# Spectra6PCB_71.net
KiCad netlist of a schematic drawn in EAGLE
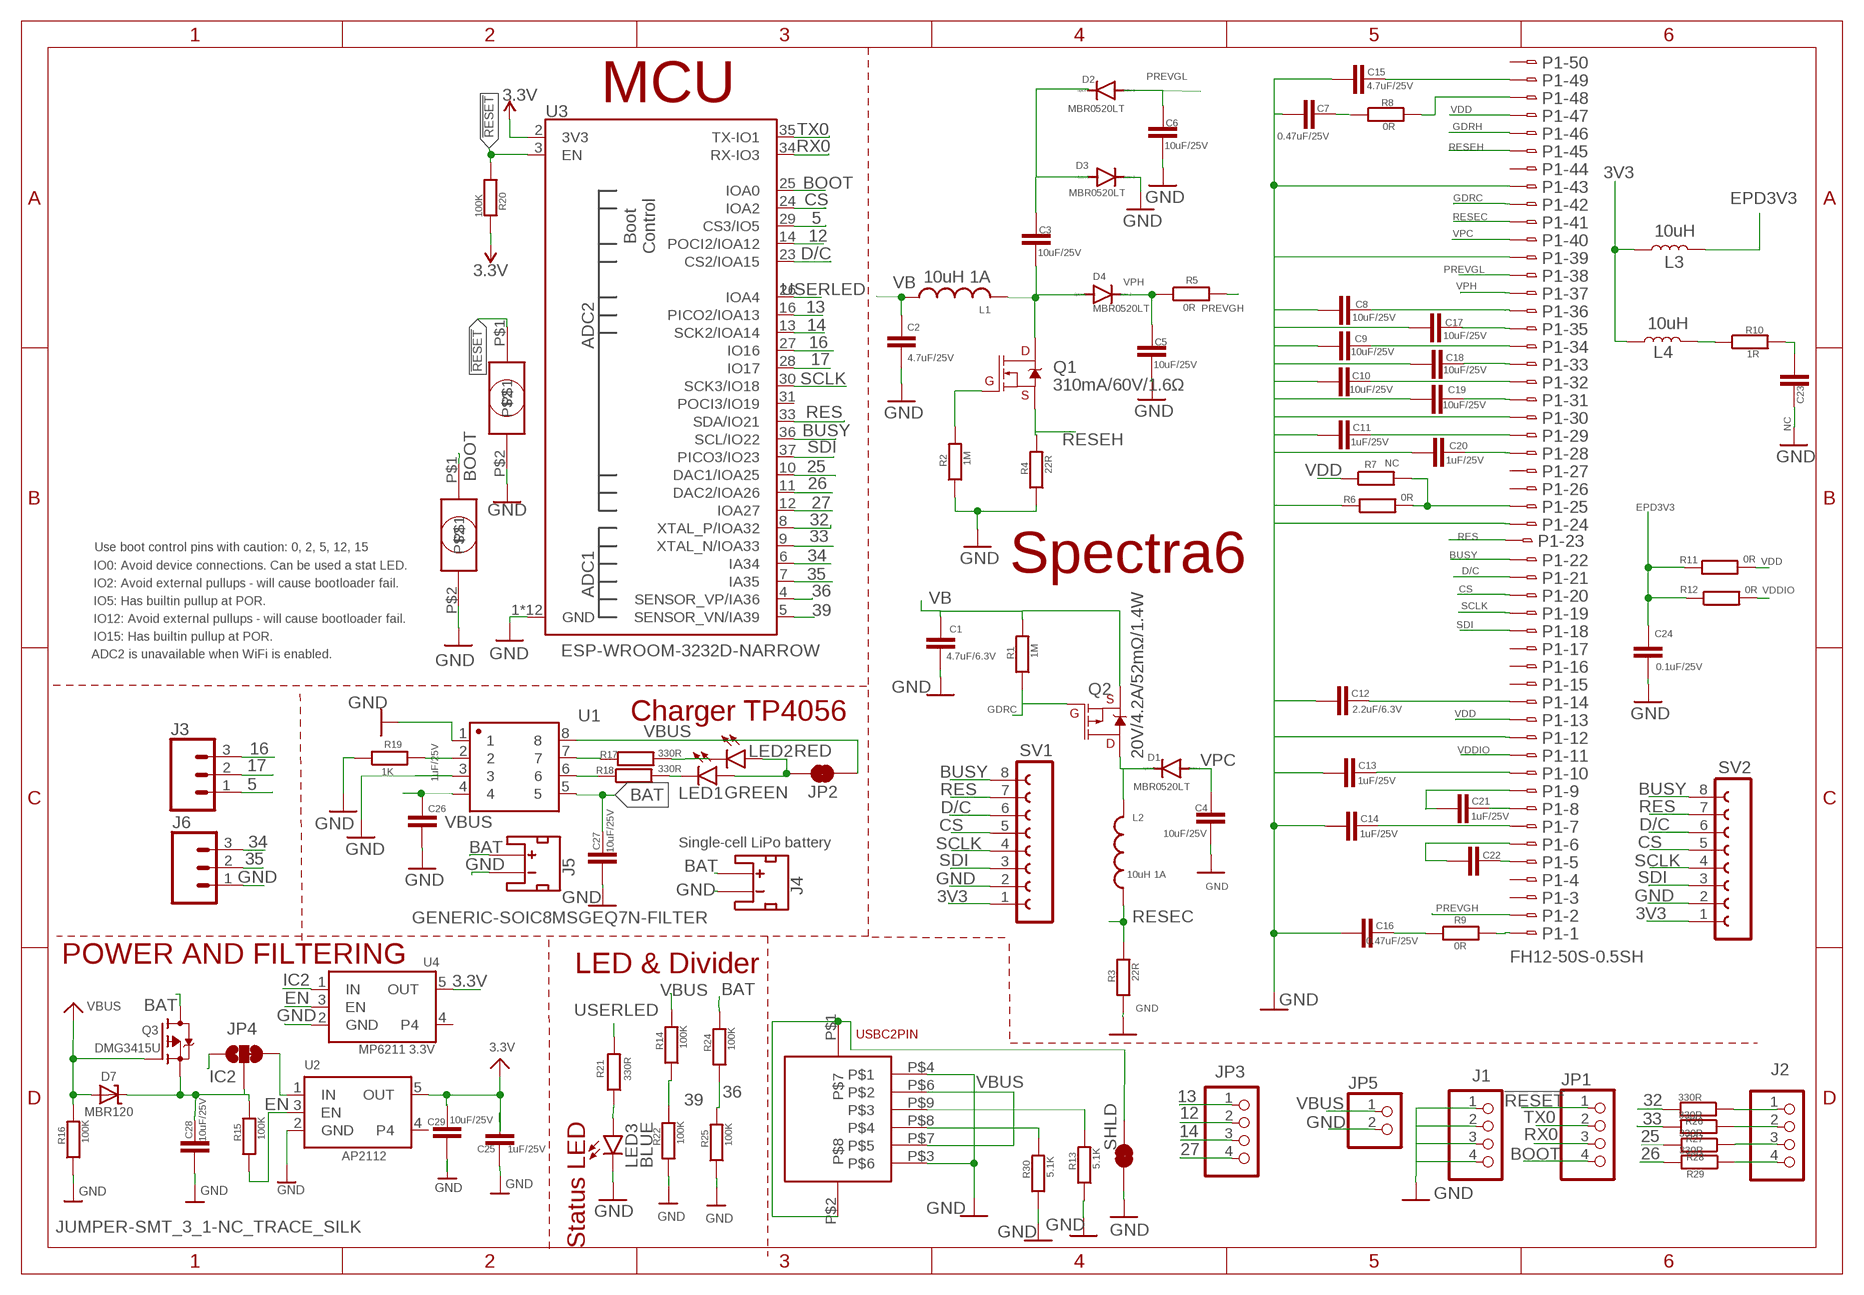
[diagram p0: schematic, sheet 1]

(export (version "E")
  (design (tool "Eeschema 10.0.6"))
  (components
    (comp (ref "C1")
      (value "4.7uF/6.3V")
      (footprint "eagle-import:C0805")
      (libsource (lib "eagle-import") (part "C-EUC0805"))
    )
    (comp (ref "C2")
      (value "4.7uF/25V")
      (footprint "eagle-import:C0805")
      (libsource (lib "eagle-import") (part "C-EUC0805"))
    )
    (comp (ref "C3")
      (value "10uF/25V")
      (footprint "eagle-import:C0805")
      (libsource (lib "eagle-import") (part "C-EUC0805"))
    )
    (comp (ref "C4")
      (value "10uF/25V")
      (footprint "eagle-import:C0805")
      (libsource (lib "eagle-import") (part "C-EUC0805"))
    )
    (comp (ref "C5")
      (value "10uF/25V")
      (footprint "eagle-import:C0805")
      (libsource (lib "eagle-import") (part "C-EUC0805"))
    )
    (comp (ref "C6")
      (value "10uF/25V")
      (footprint "eagle-import:C0805")
      (libsource (lib "eagle-import") (part "C-EUC0805"))
    )
    (comp (ref "C7")
      (value "0.47uF/25V")
      (footprint "eagle-import:C0805")
      (libsource (lib "eagle-import") (part "C-EUC0805"))
    )
    (comp (ref "C8")
      (value "10uF/25V")
      (footprint "eagle-import:C0805")
      (libsource (lib "eagle-import") (part "C-EUC0805"))
    )
    (comp (ref "C9")
      (value "10uF/25V")
      (footprint "eagle-import:C0805")
      (libsource (lib "eagle-import") (part "C-EUC0805"))
    )
    (comp (ref "C10")
      (value "10uF/25V")
      (footprint "eagle-import:C0805")
      (libsource (lib "eagle-import") (part "C-EUC0805"))
    )
    (comp (ref "C11")
      (value "1uF/25V")
      (footprint "eagle-import:C0805")
      (libsource (lib "eagle-import") (part "C-EUC0805"))
    )
    (comp (ref "C12")
      (value "2.2uF/6.3V")
      (footprint "eagle-import:C0805")
      (libsource (lib "eagle-import") (part "C-EUC0805"))
    )
    (comp (ref "C13")
      (value "1uF/25V")
      (footprint "eagle-import:C0805")
      (libsource (lib "eagle-import") (part "C-EUC0805"))
    )
    (comp (ref "C14")
      (value "1uF/25V")
      (footprint "eagle-import:C0805")
      (libsource (lib "eagle-import") (part "C-EUC0805"))
    )
    (comp (ref "C15")
      (value "4.7uF/25V")
      (footprint "eagle-import:C0805")
      (libsource (lib "eagle-import") (part "C-EUC0805"))
    )
    (comp (ref "C16")
      (value "0.47uF/25V")
      (footprint "eagle-import:C0805")
      (libsource (lib "eagle-import") (part "C-EUC0805"))
    )
    (comp (ref "C17")
      (value "10uF/25V")
      (footprint "eagle-import:C0805")
      (libsource (lib "eagle-import") (part "C-EUC0805"))
    )
    (comp (ref "C18")
      (value "10uF/25V")
      (footprint "eagle-import:C0805")
      (libsource (lib "eagle-import") (part "C-EUC0805"))
    )
    (comp (ref "C19")
      (value "10uF/25V")
      (footprint "eagle-import:C0805")
      (libsource (lib "eagle-import") (part "C-EUC0805"))
    )
    (comp (ref "C20")
      (value "1uF/25V")
      (footprint "eagle-import:C0805")
      (libsource (lib "eagle-import") (part "C-EUC0805"))
    )
    (comp (ref "C21")
      (value "1uF/25V")
      (footprint "eagle-import:C0805")
      (libsource (lib "eagle-import") (part "C-EUC0805"))
    )
    (comp (ref "C22")
      (value "1uF/25V")
      (footprint "eagle-import:C0805")
      (libsource (lib "eagle-import") (part "C-EUC0805"))
    )
    (comp (ref "C23")
      (value "NC")
      (footprint "eagle-import:C0805")
      (libsource (lib "eagle-import") (part "C-EUC0805"))
    )
    (comp (ref "C24")
      (value "0.1uF/25V")
      (footprint "eagle-import:C0805")
      (libsource (lib "eagle-import") (part "C-EUC0805"))
    )
    (comp (ref "C25")
      (value "1uF/25V")
      (footprint "eagle-import:C0805")
      (libsource (lib "eagle-import") (part "C-EUC0805"))
    )
    (comp (ref "C26")
      (value "1uF/25V")
      (footprint "eagle-import:C0805")
      (libsource (lib "eagle-import") (part "C-EUC0805"))
    )
    (comp (ref "C27")
      (value "10uF/25V")
      (footprint "eagle-import:C0805")
      (libsource (lib "eagle-import") (part "C-EUC0805"))
    )
    (comp (ref "C28")
      (value "10uF/25V")
      (footprint "eagle-import:C0805")
      (libsource (lib "eagle-import") (part "C-EUC0805"))
    )
    (comp (ref "C29")
      (value "10uF/25V")
      (footprint "eagle-import:C0805")
      (libsource (lib "eagle-import") (part "C-EUC0805"))
    )
    (comp (ref "D1")
      (value "MBR0520LT")
      (footprint "eagle-import:SOD123")
      (libsource (lib "eagle-import") (part "MBR0520LT"))
    )
    (comp (ref "D2")
      (value "MBR0520LT")
      (footprint "eagle-import:SOD123")
      (libsource (lib "eagle-import") (part "MBR0520LT"))
    )
    (comp (ref "D3")
      (value "MBR0520LT")
      (footprint "eagle-import:SOD123")
      (libsource (lib "eagle-import") (part "MBR0520LT"))
    )
    (comp (ref "D4")
      (value "MBR0520LT")
      (footprint "eagle-import:SOD123")
      (libsource (lib "eagle-import") (part "MBR0520LT"))
    )
    (comp (ref "D7")
      (value "MBR120")
      (footprint "eagle-import:SOD-123")
      (libsource (lib "eagle-import") (part "DIODE-SCHOTTKYSOD-123"))
    )
    (comp (ref "J1")
      (value "PINHD-1X4")
      (footprint "eagle-import:1X04")
      (libsource (lib "eagle-import") (part "PINHD-1X4"))
    )
    (comp (ref "J2")
      (value "PINHD-1X4")
      (footprint "eagle-import:1X04")
      (libsource (lib "eagle-import") (part "PINHD-1X4"))
    )
    (comp (ref "J3")
      (value "CONN_03PAD")
      (footprint "eagle-import:1X03_SOLDER_PADS")
      (libsource (lib "eagle-import") (part "CONN_03PAD"))
    )
    (comp (ref "J4")
      (value "JST_2MM_MALE")
      (footprint "eagle-import:JST-2-SMD")
      (libsource (lib "eagle-import") (part "JST_2MM_MALE"))
    )
    (comp (ref "J5")
      (value "NC")
      (footprint "eagle-import:JST-2-SMD")
      (libsource (lib "eagle-import") (part "JST_2MM_MALE"))
    )
    (comp (ref "J6")
      (value "CONN_03PAD")
      (footprint "eagle-import:1X03_SOLDER_PADS")
      (libsource (lib "eagle-import") (part "CONN_03PAD"))
    )
    (comp (ref "JP1")
      (value "PINHD-1X4")
      (footprint "eagle-import:1X04")
      (libsource (lib "eagle-import") (part "PINHD-1X4"))
    )
    (comp (ref "JP2")
      (value "JUMPER-SMT_2_NC_TRACE_SILK")
      (footprint "eagle-import:SMT-JUMPER_2_NC_TRACE_SILK")
      (libsource (lib "eagle-import") (part "JUMPER-SMT_2_NC_TRACE_SILK"))
    )
    (comp (ref "JP3")
      (value "PINHD-1X4")
      (footprint "eagle-import:1X04")
      (libsource (lib "eagle-import") (part "PINHD-1X4"))
    )
    (comp (ref "JP4")
      (value "JUMPER-SMT_3_1-NC_TRACE_SILK")
      (footprint "eagle-import:SMT-JUMPER_3_1-NC_TRACE_SILK")
      (libsource (lib "eagle-import") (part "JUMPER-SMT_3_1-NC_TRACE_SILK"))
    )
    (comp (ref "JP5")
      (value "PINHD-1X2")
      (footprint "eagle-import:1X02")
      (libsource (lib "eagle-import") (part "PINHD-1X2"))
    )
    (comp (ref "L1")
      (value "10uH 1A")
      (footprint "eagle-import:L4035M")
      (libsource (lib "eagle-import") (part "L-USL4035M"))
    )
    (comp (ref "L2")
      (value "10uH 1A")
      (footprint "eagle-import:L4035M")
      (libsource (lib "eagle-import") (part "L-USL4035M"))
    )
    (comp (ref "L3")
      (value "10uH")
      (footprint "eagle-import:0805")
      (libsource (lib "eagle-import") (part "INDUCTOR-0805-3.3UH"))
    )
    (comp (ref "L4")
      (value "10uH")
      (footprint "eagle-import:0805")
      (libsource (lib "eagle-import") (part "INDUCTOR-0805-3.3UH"))
    )
    (comp (ref "LED1")
      (value "GREEN")
      (footprint "eagle-import:SML0805")
      (libsource (lib "eagle-import") (part "LEDSML0805"))
    )
    (comp (ref "LED2")
      (value "RED")
      (footprint "eagle-import:SML0805")
      (libsource (lib "eagle-import") (part "LEDSML0805"))
    )
    (comp (ref "LED3")
      (value "BLUE")
      (footprint "eagle-import:SML0805")
      (libsource (lib "eagle-import") (part "LEDSML0805"))
    )
    (comp (ref "P1")
      (value "FH12-50S-0.5SH")
      (footprint "eagle-import:FH12-50S-0.5SH")
      (fields (field (name "MPN") "FH12-50S-0.5SH(55)"))
      (libsource (lib "eagle-import") (part "FH12-50S-0.5SH"))
    )
    (comp (ref "Q1")
      (value "310mA/60V/1.6Ω")
      (footprint "eagle-import:SOT323")
      (libsource (lib "eagle-import") (part "MOSFET-NCH-2N7002PW"))
    )
    (comp (ref "Q2")
      (value "20V/4.2A/52mΩ/1.4W")
      (footprint "eagle-import:SOT23-3")
      (libsource (lib "eagle-import") (part "MOSFET_PCH-DMG2305UX-7"))
    )
    (comp (ref "Q3")
      (value "DMG3415U")
      (footprint "eagle-import:SOT23-R")
      (libsource (lib "eagle-import") (part "MOSFET-P"))
    )
    (comp (ref "R1")
      (value "1M")
      (footprint "eagle-import:M0805")
      (libsource (lib "eagle-import") (part "R-EU_M0805"))
    )
    (comp (ref "R2")
      (value "1M")
      (footprint "eagle-import:M0805")
      (libsource (lib "eagle-import") (part "R-EU_M0805"))
    )
    (comp (ref "R3")
      (value "22R")
      (footprint "eagle-import:M0805")
      (libsource (lib "eagle-import") (part "R-EU_M0805"))
    )
    (comp (ref "R4")
      (value "22R")
      (footprint "eagle-import:M0805")
      (libsource (lib "eagle-import") (part "R-EU_M0805"))
    )
    (comp (ref "R5")
      (value "0R")
      (footprint "eagle-import:M0805")
      (libsource (lib "eagle-import") (part "R-EU_M0805"))
    )
    (comp (ref "R6")
      (value "0R")
      (footprint "eagle-import:M0805")
      (libsource (lib "eagle-import") (part "R-EU_M0805"))
    )
    (comp (ref "R7")
      (value "NC")
      (footprint "eagle-import:M0805")
      (libsource (lib "eagle-import") (part "R-EU_M0805"))
    )
    (comp (ref "R8")
      (value "0R")
      (footprint "eagle-import:M0805")
      (libsource (lib "eagle-import") (part "R-EU_M0805"))
    )
    (comp (ref "R9")
      (value "0R")
      (footprint "eagle-import:M0805")
      (libsource (lib "eagle-import") (part "R-EU_M0805"))
    )
    (comp (ref "R10")
      (value "1R")
      (footprint "eagle-import:M0805")
      (libsource (lib "eagle-import") (part "R-EU_M0805"))
    )
    (comp (ref "R11")
      (value "0R")
      (footprint "eagle-import:M0805")
      (libsource (lib "eagle-import") (part "R-EU_M0805"))
    )
    (comp (ref "R12")
      (value "0R")
      (footprint "eagle-import:M0805")
      (libsource (lib "eagle-import") (part "R-EU_M0805"))
    )
    (comp (ref "R13")
      (value "5.1K")
      (footprint "eagle-import:M0805")
      (libsource (lib "eagle-import") (part "R-EU_M0805"))
    )
    (comp (ref "R14")
      (value "100K")
      (footprint "eagle-import:M0805")
      (libsource (lib "eagle-import") (part "R-EU_M0805"))
    )
    (comp (ref "R15")
      (value "100K")
      (footprint "eagle-import:M0805")
      (libsource (lib "eagle-import") (part "R-EU_M0805"))
    )
    (comp (ref "R16")
      (value "100K")
      (footprint "eagle-import:M0805")
      (libsource (lib "eagle-import") (part "R-EU_M0805"))
    )
    (comp (ref "R17")
      (value "330R")
      (footprint "eagle-import:M0805")
      (libsource (lib "eagle-import") (part "R-EU_M0805"))
    )
    (comp (ref "R18")
      (value "330R")
      (footprint "eagle-import:M0805")
      (libsource (lib "eagle-import") (part "R-EU_M0805"))
    )
    (comp (ref "R19")
      (value "1K")
      (footprint "eagle-import:M0805")
      (libsource (lib "eagle-import") (part "R-EU_M0805"))
    )
    (comp (ref "R20")
      (value "100K")
      (footprint "eagle-import:M0805")
      (libsource (lib "eagle-import") (part "R-EU_M0805"))
    )
    (comp (ref "R21")
      (value "330R")
      (footprint "eagle-import:M0805")
      (libsource (lib "eagle-import") (part "R-EU_M0805"))
    )
    (comp (ref "R22")
      (value "100K")
      (footprint "eagle-import:M0805")
      (libsource (lib "eagle-import") (part "R-EU_M0805"))
    )
    (comp (ref "R24")
      (value "100K")
      (footprint "eagle-import:M0805")
      (libsource (lib "eagle-import") (part "R-EU_M0805"))
    )
    (comp (ref "R25")
      (value "100K")
      (footprint "eagle-import:M0805")
      (libsource (lib "eagle-import") (part "R-EU_M0805"))
    )
    (comp (ref "R26")
      (value "330R")
      (footprint "eagle-import:M0805")
      (libsource (lib "eagle-import") (part "R-EU_M0805"))
    )
    (comp (ref "R27")
      (value "330R")
      (footprint "eagle-import:M0805")
      (libsource (lib "eagle-import") (part "R-EU_M0805"))
    )
    (comp (ref "R28")
      (value "330R")
      (footprint "eagle-import:M0805")
      (libsource (lib "eagle-import") (part "R-EU_M0805"))
    )
    (comp (ref "R29")
      (value "330R")
      (footprint "eagle-import:M0805")
      (libsource (lib "eagle-import") (part "R-EU_M0805"))
    )
    (comp (ref "R30")
      (value "5.1K")
      (footprint "eagle-import:M0805")
      (libsource (lib "eagle-import") (part "R-EU_M0805"))
    )
    (comp (ref "S3")
      (value "TACTILE")
      (footprint "eagle-import:TACTILE")
      (libsource (lib "eagle-import") (part "TACTILE"))
    )
    (comp (ref "S4")
      (value "TACTILE")
      (footprint "eagle-import:TACTILE")
      (libsource (lib "eagle-import") (part "TACTILE"))
    )
    (comp (ref "SHLD")
      (value "SHLD")
      (footprint "eagle-import:SMT-JUMPER_2_NC_TRACE_NO-SILK")
      (libsource (lib "eagle-import") (part "JUMPER-SMT_2_NC_TRACE_NO-SILK"))
    )
    (comp (ref "SV1")
      (value "FE08-1")
      (footprint "eagle-import:FE08")
      (libsource (lib "eagle-import") (part "FE08-1"))
    )
    (comp (ref "SV2")
      (value "FE08-1")
      (footprint "eagle-import:FE08")
      (libsource (lib "eagle-import") (part "FE08-1"))
    )
    (comp (ref "U$4")
      (value "USBC6PIN")
      (footprint "eagle-import:USBC6PIN")
      (libsource (lib "eagle-import") (part "USBC6PIN"))
    )
    (comp (ref "U1")
      (value "GENERIC-SOIC8MSGEQ7N-FILTER")
      (footprint "eagle-import:SO08")
      (libsource (lib "eagle-import") (part "GENERIC-SOIC8MSGEQ7N-FILTER"))
    )
    (comp (ref "U2")
      (value "AP2112")
      (footprint "eagle-import:SOT23-5")
      (libsource (lib "eagle-import") (part "VREG_SOT23-5"))
    )
    (comp (ref "U3")
      (value "ESP-WROOM-3232D-NARROW")
      (footprint "eagle-import:ESP-WROOM-32D-NARROW")
      (libsource (lib "eagle-import") (part "ESP-WROOM-3232D-NARROW"))
    )
    (comp (ref "U4")
      (value "MP6211 3.3V")
      (footprint "eagle-import:SOT23-5")
      (libsource (lib "eagle-import") (part "VREG_SOT23-5"))
    )
  )
  (nets
    (net (code "1") (name "/3V3") (class "Default")
      (node (ref "L3") (pin "1") (pinfunction "1_1") (pintype "passive"))
      (node (ref "L4") (pin "1") (pinfunction "1_1") (pintype "passive"))
      (node (ref "SV1") (pin "1") (pinfunction "1_1") (pintype "passive"))
      (node (ref "SV2") (pin "1") (pinfunction "1_1") (pintype "passive"))
    )
    (net (code "2") (name "/5") (class "Default")
      (node (ref "J3") (pin "1") (pinfunction "1_1") (pintype "passive"))
      (node (ref "U3") (pin "29") (pinfunction "CS3/IO5_29") (pintype "bidirectional"))
    )
    (net (code "3") (name "/12") (class "Default")
      (node (ref "JP3") (pin "2") (pinfunction "2_2") (pintype "passive"))
      (node (ref "U3") (pin "14") (pinfunction "POCI2/IOA12_14") (pintype "bidirectional"))
    )
    (net (code "4") (name "/13") (class "Default")
      (node (ref "JP3") (pin "1") (pinfunction "1_1") (pintype "passive"))
      (node (ref "U3") (pin "16") (pinfunction "PICO2/IOA13_16") (pintype "bidirectional"))
    )
    (net (code "5") (name "/14") (class "Default")
      (node (ref "JP3") (pin "3") (pinfunction "3_3") (pintype "passive"))
      (node (ref "U3") (pin "13") (pinfunction "SCK2/IOA14_13") (pintype "bidirectional"))
    )
    (net (code "6") (name "/16") (class "Default")
      (node (ref "J3") (pin "3") (pinfunction "3_3") (pintype "passive"))
      (node (ref "U3") (pin "27") (pinfunction "IO16_27") (pintype "bidirectional"))
    )
    (net (code "7") (name "/17") (class "Default")
      (node (ref "J3") (pin "2") (pinfunction "2_2") (pintype "passive"))
      (node (ref "U3") (pin "28") (pinfunction "IO17_28") (pintype "bidirectional"))
    )
    (net (code "8") (name "/25") (class "Default")
      (node (ref "R28") (pin "2") (pinfunction "2_2") (pintype "passive"))
      (node (ref "U3") (pin "10") (pinfunction "DAC1/IOA25_10") (pintype "bidirectional"))
    )
    (net (code "9") (name "/26") (class "Default")
      (node (ref "R29") (pin "2") (pinfunction "2_2") (pintype "passive"))
      (node (ref "U3") (pin "11") (pinfunction "DAC2/IOA26_11") (pintype "bidirectional"))
    )
    (net (code "10") (name "/27") (class "Default")
      (node (ref "JP3") (pin "4") (pinfunction "4_4") (pintype "passive"))
      (node (ref "U3") (pin "12") (pinfunction "IOA27_12") (pintype "bidirectional"))
    )
    (net (code "11") (name "/32") (class "Default")
      (node (ref "R26") (pin "2") (pinfunction "2_2") (pintype "passive"))
      (node (ref "U3") (pin "8") (pinfunction "XTAL_P/IOA32_8") (pintype "bidirectional"))
    )
    (net (code "12") (name "/33") (class "Default")
      (node (ref "R27") (pin "2") (pinfunction "2_2") (pintype "passive"))
      (node (ref "U3") (pin "9") (pinfunction "XTAL_N/IOA33_9") (pintype "bidirectional"))
    )
    (net (code "13") (name "/34") (class "Default")
      (node (ref "J6") (pin "3") (pinfunction "3_3") (pintype "passive"))
      (node (ref "U3") (pin "6") (pinfunction "IA34_6") (pintype "bidirectional"))
    )
    (net (code "14") (name "/35") (class "Default")
      (node (ref "J6") (pin "2") (pinfunction "2_2") (pintype "passive"))
      (node (ref "U3") (pin "7") (pinfunction "IA35_7") (pintype "bidirectional"))
    )
    (net (code "15") (name "/36") (class "Default")
      (node (ref "R24") (pin "1") (pinfunction "1_1") (pintype "passive"))
      (node (ref "R25") (pin "2") (pinfunction "2_2") (pintype "passive"))
      (node (ref "U3") (pin "4") (pinfunction "SENSOR_VP/IA36_4") (pintype "bidirectional"))
    )
    (net (code "16") (name "/39") (class "Default")
      (node (ref "R14") (pin "1") (pinfunction "1_1") (pintype "passive"))
      (node (ref "R22") (pin "2") (pinfunction "2_2") (pintype "passive"))
      (node (ref "U3") (pin "5") (pinfunction "SENSOR_VN/IA39_5") (pintype "bidirectional"))
    )
    (net (code "17") (name "/BOOT") (class "Default")
      (node (ref "JP1") (pin "4") (pinfunction "4_4") (pintype "passive"))
      (node (ref "S3") (pin "P$1") (pinfunction "P$1_P$1") (pintype "bidirectional"))
      (node (ref "U3") (pin "25") (pinfunction "IOA0_25") (pintype "bidirectional"))
    )
    (net (code "18") (name "/BUSY") (class "Default")
      (node (ref "P1") (pin "22") (pinfunction "1_22") (pintype "passive"))
      (node (ref "SV1") (pin "8") (pinfunction "8_8") (pintype "passive"))
      (node (ref "SV2") (pin "8") (pinfunction "8_8") (pintype "passive"))
      (node (ref "U3") (pin "36") (pinfunction "SCL/IO22_36") (pintype "bidirectional"))
    )
    (net (code "19") (name "/CS") (class "Default")
      (node (ref "P1") (pin "20") (pinfunction "1_20") (pintype "passive"))
      (node (ref "SV1") (pin "5") (pinfunction "5_5") (pintype "passive"))
      (node (ref "SV2") (pin "5") (pinfunction "5_5") (pintype "passive"))
      (node (ref "U3") (pin "24") (pinfunction "IOA2_24") (pintype "bidirectional"))
    )
    (net (code "20") (name "/D{slash}C") (class "Default")
      (node (ref "P1") (pin "21") (pinfunction "1_21") (pintype "passive"))
      (node (ref "SV1") (pin "6") (pinfunction "6_6") (pintype "passive"))
      (node (ref "SV2") (pin "6") (pinfunction "6_6") (pintype "passive"))
      (node (ref "U3") (pin "23") (pinfunction "CS2/IOA15_23") (pintype "bidirectional"))
    )
    (net (code "21") (name "/EN") (class "Default")
      (node (ref "R15") (pin "1") (pinfunction "1_1") (pintype "passive"))
      (node (ref "U2") (pin "3") (pinfunction "EN_3") (pintype "input"))
      (node (ref "U4") (pin "3") (pinfunction "EN_3") (pintype "input"))
    )
    (net (code "22") (name "/EPD3V3") (class "Default")
      (node (ref "C24") (pin "2") (pinfunction "2_2") (pintype "passive"))
      (node (ref "L3") (pin "2") (pinfunction "2_2") (pintype "passive"))
      (node (ref "R11") (pin "1") (pinfunction "1_1") (pintype "passive"))
      (node (ref "R12") (pin "1") (pinfunction "1_1") (pintype "passive"))
    )
    (net (code "23") (name "/GDRC") (class "Default")
      (node (ref "P1") (pin "42") (pinfunction "1_42") (pintype "passive"))
      (node (ref "Q2") (pin "1") (pinfunction "G_1") (pintype "bidirectional"))
      (node (ref "R1") (pin "1") (pinfunction "1_1") (pintype "passive"))
    )
    (net (code "24") (name "/GDRH") (class "Default")
      (node (ref "P1") (pin "46") (pinfunction "1_46") (pintype "passive"))
      (node (ref "Q1") (pin "1") (pinfunction "G_1") (pintype "bidirectional"))
      (node (ref "R2") (pin "2") (pinfunction "2_2") (pintype "passive"))
    )
    (net (code "25") (name "/IC2") (class "Default")
      (node (ref "JP4") (pin "1") (pinfunction "1_1") (pintype "passive"))
      (node (ref "U4") (pin "1") (pinfunction "IN_1") (pintype "power_in"))
    )
    (net (code "26") (name "/PREVGH") (class "Default")
      (node (ref "P1") (pin "2") (pinfunction "1_2") (pintype "passive"))
      (node (ref "R5") (pin "2") (pinfunction "2_2") (pintype "passive"))
    )
    (net (code "27") (name "/PREVGL") (class "Default")
      (node (ref "C6") (pin "1") (pinfunction "1_1") (pintype "passive"))
      (node (ref "D2") (pin "A") (pinfunction "A_A") (pintype "passive"))
      (node (ref "P1") (pin "38") (pinfunction "1_38") (pintype "passive"))
    )
    (net (code "28") (name "/RES") (class "Default")
      (node (ref "P1") (pin "23") (pinfunction "1_23") (pintype "passive"))
      (node (ref "SV1") (pin "7") (pinfunction "7_7") (pintype "passive"))
      (node (ref "SV2") (pin "7") (pinfunction "7_7") (pintype "passive"))
      (node (ref "U3") (pin "33") (pinfunction "SDA/IO21_33") (pintype "bidirectional"))
    )
    (net (code "29") (name "/RESEC") (class "Default")
      (node (ref "L2") (pin "1") (pinfunction "1_1") (pintype "passive"))
      (node (ref "P1") (pin "41") (pinfunction "1_41") (pintype "passive"))
      (node (ref "R3") (pin "2") (pinfunction "2_2") (pintype "passive"))
    )
    (net (code "30") (name "/RESEH") (class "Default")
      (node (ref "P1") (pin "45") (pinfunction "1_45") (pintype "passive"))
      (node (ref "Q1") (pin "2") (pinfunction "S_2") (pintype "bidirectional"))
      (node (ref "R4") (pin "2") (pinfunction "2_2") (pintype "passive"))
    )
    (net (code "31") (name "/RX0") (class "Default")
      (node (ref "JP1") (pin "3") (pinfunction "3_3") (pintype "passive"))
      (node (ref "U3") (pin "34") (pinfunction "RX-IO3_34") (pintype "bidirectional"))
    )
    (net (code "32") (name "/SCLK") (class "Default")
      (node (ref "P1") (pin "19") (pinfunction "1_19") (pintype "passive"))
      (node (ref "SV1") (pin "4") (pinfunction "4_4") (pintype "passive"))
      (node (ref "SV2") (pin "4") (pinfunction "4_4") (pintype "passive"))
      (node (ref "U3") (pin "30") (pinfunction "SCK3/IO18_30") (pintype "bidirectional"))
    )
    (net (code "33") (name "/SDI") (class "Default")
      (node (ref "P1") (pin "18") (pinfunction "1_18") (pintype "passive"))
      (node (ref "SV1") (pin "3") (pinfunction "3_3") (pintype "passive"))
      (node (ref "SV2") (pin "3") (pinfunction "3_3") (pintype "passive"))
      (node (ref "U3") (pin "37") (pinfunction "PICO3/IO23_37") (pintype "bidirectional"))
    )
    (net (code "34") (name "/TX0") (class "Default")
      (node (ref "JP1") (pin "2") (pinfunction "2_2") (pintype "passive"))
      (node (ref "U3") (pin "35") (pinfunction "TX-IO1_35") (pintype "bidirectional"))
    )
    (net (code "35") (name "/USERLED") (class "Default")
      (node (ref "R21") (pin "2") (pinfunction "2_2") (pintype "passive"))
      (node (ref "U3") (pin "26") (pinfunction "IOA4_26") (pintype "bidirectional"))
    )
    (net (code "36") (name "/VB") (class "Default")
      (node (ref "C2") (pin "2") (pinfunction "2_2") (pintype "passive"))
      (node (ref "L1") (pin "1") (pinfunction "1_1") (pintype "passive"))
    )
    (net (code "37") (name "/VDD") (class "Default")
      (node (ref "P1") (pin "13") (pinfunction "1_13") (pintype "passive"))
      (node (ref "P1") (pin "47") (pinfunction "1_47") (pintype "passive"))
      (node (ref "R11") (pin "2") (pinfunction "2_2") (pintype "passive"))
      (node (ref "R7") (pin "1") (pinfunction "1_1") (pintype "passive"))
    )
    (net (code "38") (name "/VDDIO") (class "Default")
      (node (ref "P1") (pin "11") (pinfunction "1_11") (pintype "passive"))
      (node (ref "R12") (pin "2") (pinfunction "2_2") (pintype "passive"))
    )
    (net (code "39") (name "/VPC") (class "Default")
      (node (ref "C4") (pin "2") (pinfunction "2_2") (pintype "passive"))
      (node (ref "D1") (pin "A") (pinfunction "A_A") (pintype "passive"))
      (node (ref "P1") (pin "40") (pinfunction "1_40") (pintype "passive"))
    )
    (net (code "40") (name "/VPH") (class "Default")
      (node (ref "C5") (pin "1") (pinfunction "1_1") (pintype "passive"))
      (node (ref "D4") (pin "C") (pinfunction "C_C") (pintype "passive"))
      (node (ref "P1") (pin "37") (pinfunction "1_37") (pintype "passive"))
      (node (ref "R5") (pin "1") (pinfunction "1_1") (pintype "passive"))
    )
    (net (code "41") (name "/~{RESET}") (class "Default")
      (node (ref "JP1") (pin "1") (pinfunction "1_1") (pintype "passive"))
      (node (ref "R20") (pin "1") (pinfunction "1_1") (pintype "passive"))
      (node (ref "S4") (pin "P$1") (pinfunction "P$1_P$1") (pintype "bidirectional"))
      (node (ref "U3") (pin "3") (pinfunction "EN_3") (pintype "bidirectional"))
    )
    (net (code "42") (name "3.3V") (class "Default")
      (node (ref "C25") (pin "2") (pinfunction "2_2") (pintype "passive"))
      (node (ref "C29") (pin "2") (pinfunction "2_2") (pintype "passive"))
      (node (ref "R20") (pin "2") (pinfunction "2_2") (pintype "passive"))
      (node (ref "U2") (pin "5") (pinfunction "OUT_5") (pintype "power_in"))
      (node (ref "U3") (pin "2") (pinfunction "3V3_2") (pintype "bidirectional"))
      (node (ref "U4") (pin "5") (pinfunction "OUT_5") (pintype "power_in"))
    )
    (net (code "43") (name "BAT") (class "Default")
      (node (ref "C27") (pin "2") (pinfunction "2_2") (pintype "passive"))
      (node (ref "J4") (pin "2") (pinfunction "+_2") (pintype "bidirectional"))
      (node (ref "J5") (pin "2") (pinfunction "+_2") (pintype "bidirectional"))
      (node (ref "Q3") (pin "3") (pinfunction "D_3") (pintype "passive"))
      (node (ref "R24") (pin "2") (pinfunction "2_2") (pintype "passive"))
      (node (ref "U1") (pin "5") (pinfunction "5_5") (pintype "bidirectional"))
    )
    (net (code "44") (name "GND") (class "Default")
      (node (ref "C1") (pin "1") (pinfunction "1_1") (pintype "passive"))
      (node (ref "C10") (pin "1") (pinfunction "1_1") (pintype "passive"))
      (node (ref "C11") (pin "1") (pinfunction "1_1") (pintype "passive"))
      (node (ref "C12") (pin "1") (pinfunction "1_1") (pintype "passive"))
      (node (ref "C13") (pin "1") (pinfunction "1_1") (pintype "passive"))
      (node (ref "C14") (pin "1") (pinfunction "1_1") (pintype "passive"))
      (node (ref "C15") (pin "1") (pinfunction "1_1") (pintype "passive"))
      (node (ref "C16") (pin "1") (pinfunction "1_1") (pintype "passive"))
      (node (ref "C17") (pin "1") (pinfunction "1_1") (pintype "passive"))
      (node (ref "C18") (pin "1") (pinfunction "1_1") (pintype "passive"))
      (node (ref "C19") (pin "1") (pinfunction "1_1") (pintype "passive"))
      (node (ref "C2") (pin "1") (pinfunction "1_1") (pintype "passive"))
      (node (ref "C20") (pin "1") (pinfunction "1_1") (pintype "passive"))
      (node (ref "C23") (pin "2") (pinfunction "2_2") (pintype "passive"))
      (node (ref "C24") (pin "1") (pinfunction "1_1") (pintype "passive"))
      (node (ref "C25") (pin "1") (pinfunction "1_1") (pintype "passive"))
      (node (ref "C26") (pin "1") (pinfunction "1_1") (pintype "passive"))
      (node (ref "C27") (pin "1") (pinfunction "1_1") (pintype "passive"))
      (node (ref "C28") (pin "1") (pinfunction "1_1") (pintype "passive"))
      (node (ref "C29") (pin "1") (pinfunction "1_1") (pintype "passive"))
      (node (ref "C4") (pin "1") (pinfunction "1_1") (pintype "passive"))
      (node (ref "C5") (pin "2") (pinfunction "2_2") (pintype "passive"))
      (node (ref "C6") (pin "2") (pinfunction "2_2") (pintype "passive"))
      (node (ref "C7") (pin "1") (pinfunction "1_1") (pintype "passive"))
      (node (ref "C8") (pin "1") (pinfunction "1_1") (pintype "passive"))
      (node (ref "C9") (pin "1") (pinfunction "1_1") (pintype "passive"))
      (node (ref "D3") (pin "C") (pinfunction "C_C") (pintype "passive"))
      (node (ref "J1") (pin "1") (pinfunction "1_1") (pintype "passive"))
      (node (ref "J1") (pin "2") (pinfunction "2_2") (pintype "passive"))
      (node (ref "J1") (pin "3") (pinfunction "3_3") (pintype "passive"))
      (node (ref "J1") (pin "4") (pinfunction "4_4") (pintype "passive"))
      (node (ref "J4") (pin "1") (pinfunction "-_1") (pintype "bidirectional"))
      (node (ref "J5") (pin "1") (pinfunction "-_1") (pintype "bidirectional"))
      (node (ref "J6") (pin "1") (pinfunction "1_1") (pintype "passive"))
      (node (ref "JP5") (pin "2") (pinfunction "2_2") (pintype "passive"))
      (node (ref "LED3") (pin "C") (pinfunction "C_C") (pintype "passive"))
      (node (ref "P1") (pin "24") (pinfunction "1_24") (pintype "passive"))
      (node (ref "P1") (pin "30") (pinfunction "1_30") (pintype "passive"))
      (node (ref "P1") (pin "39") (pinfunction "1_39") (pintype "passive"))
      (node (ref "P1") (pin "43") (pinfunction "1_43") (pintype "passive"))
      (node (ref "R13") (pin "1") (pinfunction "1_1") (pintype "passive"))
      (node (ref "R16") (pin "1") (pinfunction "1_1") (pintype "passive"))
      (node (ref "R19") (pin "1") (pinfunction "1_1") (pintype "passive"))
      (node (ref "R2") (pin "1") (pinfunction "1_1") (pintype "passive"))
      (node (ref "R22") (pin "1") (pinfunction "1_1") (pintype "passive"))
      (node (ref "R25") (pin "1") (pinfunction "1_1") (pintype "passive"))
      (node (ref "R3") (pin "1") (pinfunction "1_1") (pintype "passive"))
      (node (ref "R30") (pin "1") (pinfunction "1_1") (pintype "passive"))
      (node (ref "R4") (pin "1") (pinfunction "1_1") (pintype "passive"))
      (node (ref "R6") (pin "1") (pinfunction "1_1") (pintype "passive"))
      (node (ref "S3") (pin "P$2") (pinfunction "P$2_P$2") (pintype "bidirectional"))
      (node (ref "S4") (pin "P$2") (pinfunction "P$2_P$2") (pintype "bidirectional"))
      (node (ref "SHLD") (pin "1") (pinfunction "1_1") (pintype "passive"))
      (node (ref "SV1") (pin "2") (pinfunction "2_2") (pintype "passive"))
      (node (ref "SV2") (pin "2") (pinfunction "2_2") (pintype "passive"))
      (node (ref "U$4") (pin "P$3") (pinfunction "P$6_P$3") (pintype "bidirectional"))
      (node (ref "U$4") (pin "P$4") (pinfunction "P$1_P$4") (pintype "bidirectional"))
      (node (ref "U1") (pin "1") (pinfunction "1_1") (pintype "bidirectional"))
      (node (ref "U1") (pin "3") (pinfunction "3_3") (pintype "bidirectional"))
      (node (ref "U2") (pin "2") (pinfunction "GND_2") (pintype "power_in"))
      (node (ref "U3") (pin "1") (pinfunction "GND_1") (pintype "bidirectional"))
      (node (ref "U3") (pin "15") (pinfunction "GND_15") (pintype "bidirectional"))
      (node (ref "U3") (pin "38") (pinfunction "GND_38") (pintype "bidirectional"))
      (node (ref "U3") (pin "GND1") (pinfunction "GND_GND1") (pintype "bidirectional"))
      (node (ref "U3") (pin "GNDT1") (pinfunction "GND_GNDT1") (pintype "bidirectional"))
      (node (ref "U3") (pin "GNDT2") (pinfunction "GND_GNDT2") (pintype "bidirectional"))
      (node (ref "U3") (pin "GNDT3") (pinfunction "GND_GNDT3") (pintype "bidirectional"))
      (node (ref "U3") (pin "GNDT4") (pinfunction "GND_GNDT4") (pintype "bidirectional"))
      (node (ref "U3") (pin "GNDT5") (pinfunction "GND_GNDT5") (pintype "bidirectional"))
      (node (ref "U3") (pin "GNDT6") (pinfunction "GND_GNDT6") (pintype "bidirectional"))
      (node (ref "U3") (pin "GNDT7") (pinfunction "GND_GNDT7") (pintype "bidirectional"))
      (node (ref "U3") (pin "GNDT8") (pinfunction "GND_GNDT8") (pintype "bidirectional"))
      (node (ref "U4") (pin "2") (pinfunction "GND_2") (pintype "power_in"))
    )
    (net (code "45") (name "Net-(C3-Pad1)") (class "Default")
      (node (ref "C3") (pin "1") (pinfunction "1_1") (pintype "passive"))
      (node (ref "D2") (pin "C") (pinfunction "C_C") (pintype "passive"))
      (node (ref "D3") (pin "A") (pinfunction "A_A") (pintype "passive"))
    )
    (net (code "46") (name "Net-(C7-Pad2)") (class "Default")
      (node (ref "C7") (pin "2") (pinfunction "2_2") (pintype "passive"))
      (node (ref "R8") (pin "1") (pinfunction "1_1") (pintype "passive"))
    )
    (net (code "47") (name "Net-(C16-Pad2)") (class "Default")
      (node (ref "C16") (pin "2") (pinfunction "2_2") (pintype "passive"))
      (node (ref "R9") (pin "1") (pinfunction "1_1") (pintype "passive"))
    )
    (net (code "48") (name "Net-(C23-Pad1)") (class "Default")
      (node (ref "C23") (pin "1") (pinfunction "1_1") (pintype "passive"))
      (node (ref "R10") (pin "2") (pinfunction "2_2") (pintype "passive"))
    )
    (net (code "49") (name "Net-(J2-Pad1)") (class "Default")
      (node (ref "J2") (pin "1") (pinfunction "1_1") (pintype "passive"))
      (node (ref "R26") (pin "1") (pinfunction "1_1") (pintype "passive"))
    )
    (net (code "50") (name "Net-(J2-Pad2)") (class "Default")
      (node (ref "J2") (pin "2") (pinfunction "2_2") (pintype "passive"))
      (node (ref "R27") (pin "1") (pinfunction "1_1") (pintype "passive"))
    )
    (net (code "51") (name "Net-(J2-Pad3)") (class "Default")
      (node (ref "J2") (pin "3") (pinfunction "3_3") (pintype "passive"))
      (node (ref "R28") (pin "1") (pinfunction "1_1") (pintype "passive"))
    )
    (net (code "52") (name "Net-(J2-Pad4)") (class "Default")
      (node (ref "J2") (pin "4") (pinfunction "4_4") (pintype "passive"))
      (node (ref "R29") (pin "1") (pinfunction "1_1") (pintype "passive"))
    )
    (net (code "53") (name "Net-(JP2-Pad2)") (class "Default")
      (node (ref "JP2") (pin "2") (pinfunction "2_2") (pintype "passive"))
      (node (ref "LED1") (pin "A") (pinfunction "A_A") (pintype "passive"))
      (node (ref "LED2") (pin "A") (pinfunction "A_A") (pintype "passive"))
    )
    (net (code "54") (name "Net-(L4-Pad2)") (class "Default")
      (node (ref "L4") (pin "2") (pinfunction "2_2") (pintype "passive"))
      (node (ref "R10") (pin "1") (pinfunction "1_1") (pintype "passive"))
    )
    (net (code "55") (name "Net-(LED1-PadC)") (class "Default")
      (node (ref "LED1") (pin "C") (pinfunction "C_C") (pintype "passive"))
      (node (ref "R18") (pin "2") (pinfunction "2_2") (pintype "passive"))
    )
    (net (code "56") (name "Net-(LED2-PadC)") (class "Default")
      (node (ref "LED2") (pin "C") (pinfunction "C_C") (pintype "passive"))
      (node (ref "R17") (pin "2") (pinfunction "2_2") (pintype "passive"))
    )
    (net (code "57") (name "Net-(LED3-PadA)") (class "Default")
      (node (ref "LED3") (pin "A") (pinfunction "A_A") (pintype "passive"))
      (node (ref "R21") (pin "1") (pinfunction "1_1") (pintype "passive"))
    )
    (net (code "58") (name "Net-(P1-Pad1)") (class "Default")
      (node (ref "P1") (pin "1") (pinfunction "1_1") (pintype "passive"))
      (node (ref "R9") (pin "2") (pinfunction "2_2") (pintype "passive"))
    )
    (net (code "59") (name "Net-(P1AA-1)") (class "Default")
      (node (ref "C18") (pin "2") (pinfunction "2_2") (pintype "passive"))
      (node (ref "P1") (pin "33") (pinfunction "1_33") (pintype "passive"))
    )
    (net (code "60") (name "Net-(P1AB-1)") (class "Default")
      (node (ref "C9") (pin "2") (pinfunction "2_2") (pintype "passive"))
      (node (ref "P1") (pin "34") (pinfunction "1_34") (pintype "passive"))
    )
    (net (code "61") (name "Net-(P1AC-1)") (class "Default")
      (node (ref "C17") (pin "2") (pinfunction "2_2") (pintype "passive"))
      (node (ref "P1") (pin "35") (pinfunction "1_35") (pintype "passive"))
    )
    (net (code "62") (name "Net-(P1AD-1)") (class "Default")
      (node (ref "C8") (pin "2") (pinfunction "2_2") (pintype "passive"))
      (node (ref "P1") (pin "36") (pinfunction "1_36") (pintype "passive"))
    )
    (net (code "63") (name "Net-(P1AQ-1)") (class "Default")
      (node (ref "P1") (pin "48") (pinfunction "1_48") (pintype "passive"))
      (node (ref "R8") (pin "2") (pinfunction "2_2") (pintype "passive"))
    )
    (net (code "64") (name "Net-(P1AR-1)") (class "Default")
      (node (ref "C15") (pin "2") (pinfunction "2_2") (pintype "passive"))
      (node (ref "P1") (pin "49") (pinfunction "1_49") (pintype "passive"))
    )
    (net (code "65") (name "Net-(P1AS-1)") (class "Default")
      (node (ref "C22") (pin "2") (pinfunction "2_2") (pintype "passive"))
      (node (ref "P1") (pin "5") (pinfunction "1_5") (pintype "passive"))
    )
    (net (code "66") (name "Net-(P1AU-1)") (class "Default")
      (node (ref "C22") (pin "1") (pinfunction "1_1") (pintype "passive"))
      (node (ref "P1") (pin "6") (pinfunction "1_6") (pintype "passive"))
    )
    (net (code "67") (name "Net-(P1AV-1)") (class "Default")
      (node (ref "C14") (pin "2") (pinfunction "2_2") (pintype "passive"))
      (node (ref "P1") (pin "7") (pinfunction "1_7") (pintype "passive"))
    )
    (net (code "68") (name "Net-(P1AW-1)") (class "Default")
      (node (ref "C21") (pin "2") (pinfunction "2_2") (pintype "passive"))
      (node (ref "P1") (pin "8") (pinfunction "1_8") (pintype "passive"))
    )
    (net (code "69") (name "Net-(P1AX-1)") (class "Default")
      (node (ref "C21") (pin "1") (pinfunction "1_1") (pintype "passive"))
      (node (ref "P1") (pin "9") (pinfunction "1_9") (pintype "passive"))
    )
    (net (code "70") (name "Net-(P1B-1)") (class "Default")
      (node (ref "C13") (pin "2") (pinfunction "2_2") (pintype "passive"))
      (node (ref "P1") (pin "10") (pinfunction "1_10") (pintype "passive"))
    )
    (net (code "71") (name "Net-(P1F-1)") (class "Default")
      (node (ref "C12") (pin "2") (pinfunction "2_2") (pintype "passive"))
      (node (ref "P1") (pin "14") (pinfunction "1_14") (pintype "passive"))
    )
    (net (code "72") (name "Net-(P1R-1)") (class "Default")
      (node (ref "P1") (pin "25") (pinfunction "1_25") (pintype "passive"))
      (node (ref "R6") (pin "2") (pinfunction "2_2") (pintype "passive"))
      (node (ref "R7") (pin "2") (pinfunction "2_2") (pintype "passive"))
    )
    (net (code "73") (name "Net-(P1U-1)") (class "Default")
      (node (ref "C20") (pin "2") (pinfunction "2_2") (pintype "passive"))
      (node (ref "P1") (pin "28") (pinfunction "1_28") (pintype "passive"))
    )
    (net (code "74") (name "Net-(P1V-1)") (class "Default")
      (node (ref "C11") (pin "2") (pinfunction "2_2") (pintype "passive"))
      (node (ref "P1") (pin "29") (pinfunction "1_29") (pintype "passive"))
    )
    (net (code "75") (name "Net-(P1Y-1)") (class "Default")
      (node (ref "C19") (pin "2") (pinfunction "2_2") (pintype "passive"))
      (node (ref "P1") (pin "31") (pinfunction "1_31") (pintype "passive"))
    )
    (net (code "76") (name "Net-(P1Z-1)") (class "Default")
      (node (ref "C10") (pin "2") (pinfunction "2_2") (pintype "passive"))
      (node (ref "P1") (pin "32") (pinfunction "1_32") (pintype "passive"))
    )
    (net (code "77") (name "Net-(Q1-D)") (class "Default")
      (node (ref "C3") (pin "2") (pinfunction "2_2") (pintype "passive"))
      (node (ref "D4") (pin "A") (pinfunction "A_A") (pintype "passive"))
      (node (ref "L1") (pin "2") (pinfunction "2_2") (pintype "passive"))
      (node (ref "Q1") (pin "3") (pinfunction "D_3") (pintype "bidirectional"))
    )
    (net (code "78") (name "Net-(Q2-D)") (class "Default")
      (node (ref "D1") (pin "C") (pinfunction "C_C") (pintype "passive"))
      (node (ref "L2") (pin "2") (pinfunction "2_2") (pintype "passive"))
      (node (ref "Q2") (pin "3") (pinfunction "D_3") (pintype "bidirectional"))
    )
    (net (code "79") (name "Net-(Q2-S)") (class "Default")
      (node (ref "C1") (pin "2") (pinfunction "2_2") (pintype "passive"))
      (node (ref "Q2") (pin "2") (pinfunction "S_2") (pintype "bidirectional"))
      (node (ref "R1") (pin "2") (pinfunction "2_2") (pintype "passive"))
    )
    (net (code "80") (name "Net-(Q3-S)") (class "Default")
      (node (ref "C28") (pin "2") (pinfunction "2_2") (pintype "passive"))
      (node (ref "D7") (pin "C") (pinfunction "C_C") (pintype "passive"))
      (node (ref "JP4") (pin "2") (pinfunction "2_2") (pintype "passive"))
      (node (ref "Q3") (pin "2") (pinfunction "S_2") (pintype "passive"))
      (node (ref "R15") (pin "2") (pinfunction "2_2") (pintype "passive"))
    )
    (net (code "81") (name "Net-(R17-Pad1)") (class "Default")
      (node (ref "R17") (pin "1") (pinfunction "1_1") (pintype "passive"))
      (node (ref "U1") (pin "7") (pinfunction "7_7") (pintype "bidirectional"))
    )
    (net (code "82") (name "Net-(R18-Pad1)") (class "Default")
      (node (ref "R18") (pin "1") (pinfunction "1_1") (pintype "passive"))
      (node (ref "U1") (pin "6") (pinfunction "6_6") (pintype "bidirectional"))
    )
    (net (code "83") (name "Net-(R19-Pad2)") (class "Default")
      (node (ref "R19") (pin "2") (pinfunction "2_2") (pintype "passive"))
      (node (ref "U1") (pin "2") (pinfunction "2_2") (pintype "bidirectional"))
    )
    (net (code "84") (name "Net-(U$4-P$3)") (class "Default")
      (node (ref "R13") (pin "2") (pinfunction "2_2") (pintype "passive"))
      (node (ref "U$4") (pin "P$9") (pinfunction "P$3_P$9") (pintype "bidirectional"))
    )
    (net (code "85") (name "Net-(U$4-P$4)") (class "Default")
      (node (ref "R30") (pin "2") (pinfunction "2_2") (pintype "passive"))
      (node (ref "U$4") (pin "P$8") (pinfunction "P$4_P$8") (pintype "bidirectional"))
    )
    (net (code "86") (name "Net-(U$4-P$7)") (class "Default")
      (node (ref "SHLD") (pin "2") (pinfunction "2_2") (pintype "passive"))
      (node (ref "U$4") (pin "P$1") (pinfunction "P$7_P$1") (pintype "bidirectional"))
      (node (ref "U$4") (pin "P$2") (pinfunction "P$8_P$2") (pintype "bidirectional"))
    )
    (net (code "87") (name "Net-(U2-IN)") (class "Default")
      (node (ref "JP4") (pin "3") (pinfunction "3_3") (pintype "passive"))
      (node (ref "U2") (pin "1") (pinfunction "IN_1") (pintype "power_in"))
    )
    (net (code "88") (name "VBUS") (class "Default")
      (node (ref "C26") (pin "2") (pinfunction "2_2") (pintype "passive"))
      (node (ref "D7") (pin "A") (pinfunction "A_A") (pintype "passive"))
      (node (ref "JP2") (pin "1") (pinfunction "1_1") (pintype "passive"))
      (node (ref "JP5") (pin "1") (pinfunction "1_1") (pintype "passive"))
      (node (ref "Q3") (pin "1") (pinfunction "G_1") (pintype "passive"))
      (node (ref "R14") (pin "2") (pinfunction "2_2") (pintype "passive"))
      (node (ref "R16") (pin "2") (pinfunction "2_2") (pintype "passive"))
      (node (ref "U$4") (pin "P$6") (pinfunction "P$2_P$6") (pintype "bidirectional"))
      (node (ref "U$4") (pin "P$7") (pinfunction "P$5_P$7") (pintype "bidirectional"))
      (node (ref "U1") (pin "4") (pinfunction "4_4") (pintype "bidirectional"))
      (node (ref "U1") (pin "8") (pinfunction "8_8") (pintype "bidirectional"))
    )
    (net (code "89") (name "unconnected-(J4-PAD1-PadNC1)") (class "Default")
      (node (ref "J4") (pin "NC1") (pinfunction "PAD1_NC1") (pintype "bidirectional"))
    )
    (net (code "90") (name "unconnected-(J4-PAD2-PadNC2)") (class "Default")
      (node (ref "J4") (pin "NC2") (pinfunction "PAD2_NC2") (pintype "bidirectional"))
    )
    (net (code "91") (name "unconnected-(J5-PAD1-PadNC1)") (class "Default")
      (node (ref "J5") (pin "NC1") (pinfunction "PAD1_NC1") (pintype "bidirectional"))
    )
    (net (code "92") (name "unconnected-(J5-PAD2-PadNC2)") (class "Default")
      (node (ref "J5") (pin "NC2") (pinfunction "PAD2_NC2") (pintype "bidirectional"))
    )
    (net (code "93") (name "unconnected-(P1AH-1-Pad4)") (class "Default")
      (node (ref "P1") (pin "4") (pinfunction "1_4") (pintype "passive"))
    )
    (net (code "94") (name "unconnected-(P1AM-1-Pad44)") (class "Default")
      (node (ref "P1") (pin "44") (pinfunction "1_44") (pintype "passive"))
    )
    (net (code "95") (name "unconnected-(P1AT-1-Pad50)") (class "Default")
      (node (ref "P1") (pin "50") (pinfunction "1_50") (pintype "passive"))
    )
    (net (code "96") (name "unconnected-(P1D-1-Pad12)") (class "Default")
      (node (ref "P1") (pin "12") (pinfunction "1_12") (pintype "passive"))
    )
    (net (code "97") (name "unconnected-(P1G-1-Pad15)") (class "Default")
      (node (ref "P1") (pin "15") (pinfunction "1_15") (pintype "passive"))
    )
    (net (code "98") (name "unconnected-(P1H-1-Pad16)") (class "Default")
      (node (ref "P1") (pin "16") (pinfunction "1_16") (pintype "passive"))
    )
    (net (code "99") (name "unconnected-(P1I-1-Pad17)") (class "Default")
      (node (ref "P1") (pin "17") (pinfunction "1_17") (pintype "passive"))
    )
    (net (code "100") (name "unconnected-(P1S-1-Pad26)") (class "Default")
      (node (ref "P1") (pin "26") (pinfunction "1_26") (pintype "passive"))
    )
    (net (code "101") (name "unconnected-(P1T-1-Pad27)") (class "Default")
      (node (ref "P1") (pin "27") (pinfunction "1_27") (pintype "passive"))
    )
    (net (code "102") (name "unconnected-(P1W-1-Pad3)") (class "Default")
      (node (ref "P1") (pin "3") (pinfunction "1_3") (pintype "passive"))
    )
    (net (code "103") (name "unconnected-(U2-P4-Pad4)") (class "Default")
      (node (ref "U2") (pin "4") (pinfunction "P4_4") (pintype "bidirectional"))
    )
    (net (code "104") (name "unconnected-(U3-POCI3{slash}IO19-Pad31)") (class "Default")
      (node (ref "U3") (pin "31") (pinfunction "POCI3/IO19_31") (pintype "bidirectional"))
    )
    (net (code "105") (name "unconnected-(U4-P4-Pad4)") (class "Default")
      (node (ref "U4") (pin "4") (pinfunction "P4_4") (pintype "bidirectional"))
    )
  )
)
